# TIDA01398_POWER_PIR.net
KiCad netlist of a schematic drawn in Altium Designer
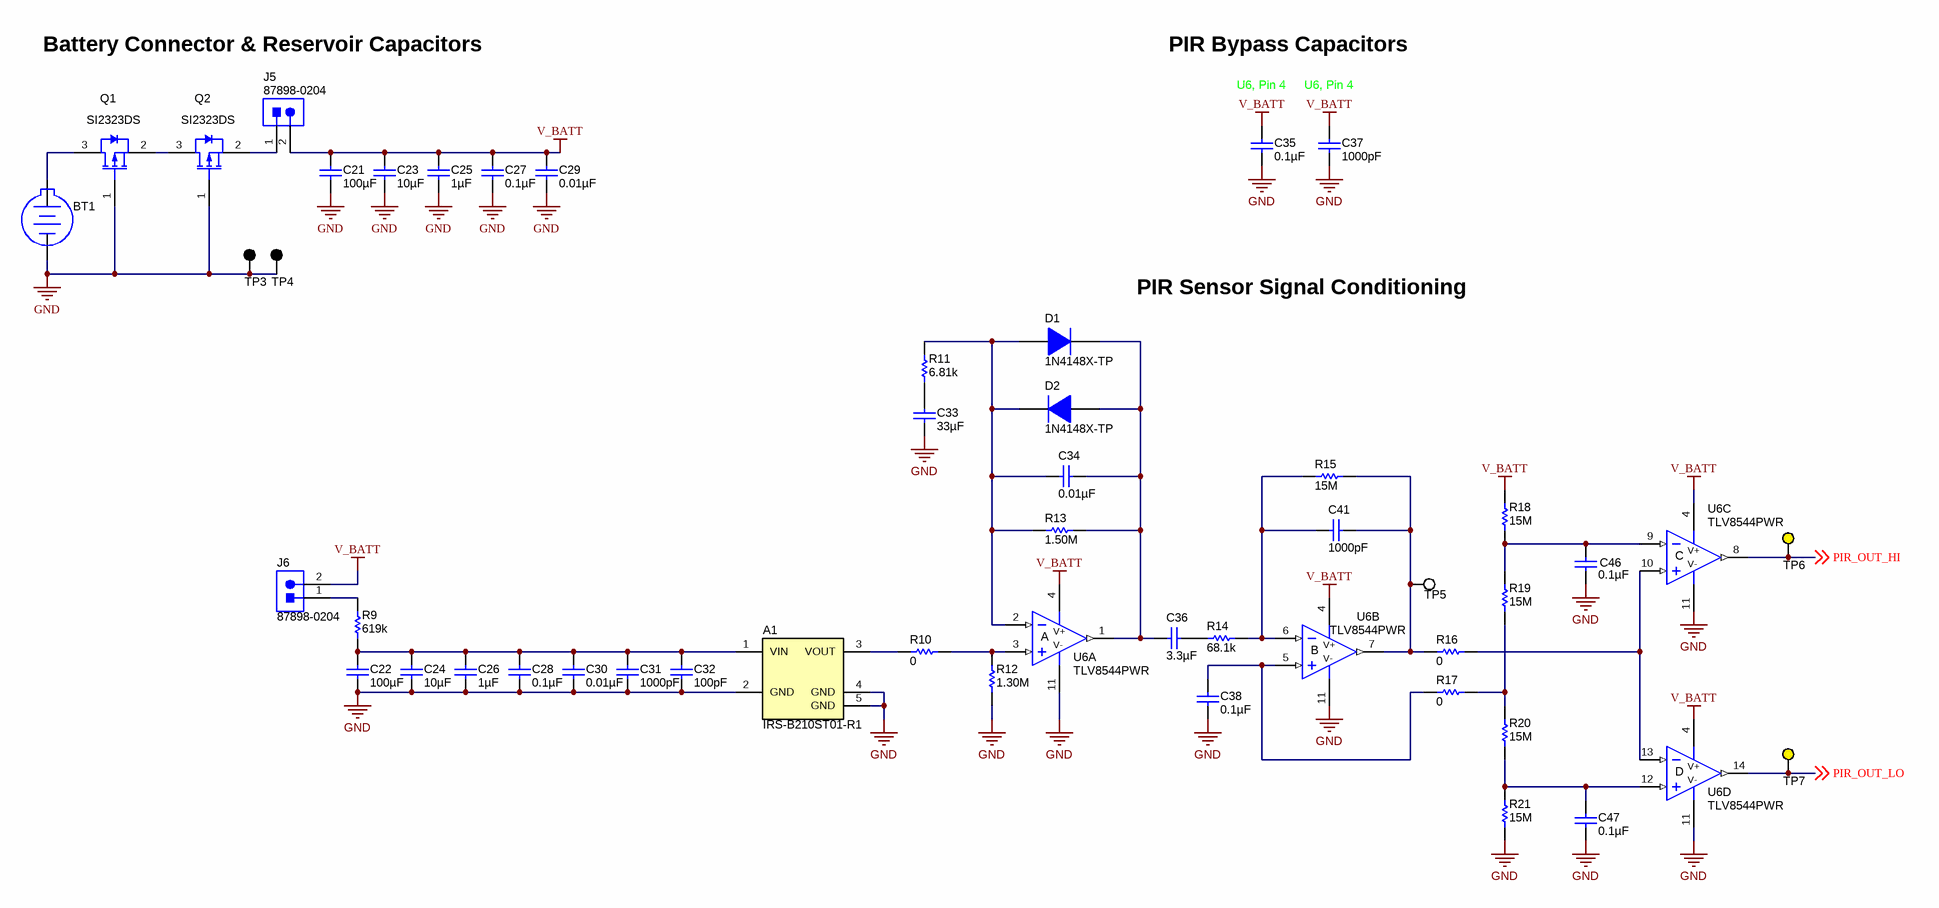
[diagram p0: TIDA01398_POWER_PIR.SchDoc]

(export (version "E")
  (design (tool "Eeschema 10.0.6"))
  (components
    (comp (ref "A1")
      (value "IRS-B210ST01-R1")
      (footprint "Murata_IRS-B210ST01")
      (description "Pyroelectric Infrared Sensors for Reflow Soldering, 3.6mVp-p, SMD")
      (fields
        (field (name "MANUFACTURER") "MuRata")
        (field (name "SYMBOLCREATOR") "Altium")
        (field (name "PUBLISHER") "Texas Instruments")
      )
      (libsource (lib "Other_Passive") (part "IRS-B210ST01-R1"))
    )
    (comp (ref "BT1")
      (value "BS-7")
      (footprint "BAT_BS-7")
      (description "Battery Holder, CR2032, Retainer clip, TH")
      (fields
        (field (name "MANUFACTURER") "Memory Protection Devices")
        (field (name "SYMBOLCREATOR") "a0412235")
        (field (name "PUBLISHER") "Texas Instruments")
      )
      (libsource (lib "Hardware") (part "BS-7"))
    )
    (comp (ref "C21")
      (value "C3216X5R1A107M160AC")
      (footprint "1206_190")
      (description "CAP, CERM, 100 µF, 10 V, +/- 20%, X5R, 1206_190")
      (fields
        (field (name "MANUFACTURER") "TDK")
        (field (name "VALUEDISPLAYED") "100µF")
        (field (name "PUBLISHER") "Texas Instruments")
      )
      (libsource (lib "Capacitor_Ceramic") (part "C3216X5R1A107M160AC"))
    )
    (comp (ref "C22")
      (value "C3216X5R1A107M160AC")
      (footprint "1206_190")
      (description "CAP, CERM, 100 µF, 10 V, +/- 20%, X5R, 1206_190")
      (fields
        (field (name "MANUFACTURER") "TDK")
        (field (name "VALUEDISPLAYED") "100µF")
        (field (name "PUBLISHER") "Texas Instruments")
      )
      (libsource (lib "Capacitor_Ceramic") (part "C3216X5R1A107M160AC"))
    )
    (comp (ref "C23")
      (value "C1608X5R0J106M")
      (footprint "0603")
      (description "CAP, CERM, 10 µF, 6.3 V, +/- 20%, X5R, 0603")
      (fields
        (field (name "VALUEDISPLAYED") "10µF")
        (field (name "MANUFACTURER") "TDK")
        (field (name "PUBLISHER") "Texas Instruments")
      )
      (libsource (lib "Capacitor_Ceramic") (part "C1608X5R0J106M"))
    )
    (comp (ref "C24")
      (value "GRM155R60J106ME44D")
      (footprint "0402")
      (description "CAP, CERM, 10 µF, 6.3 V, +/- 20%, X5R, 0402")
      (fields
        (field (name "VALUEDISPLAYED") "10µF")
        (field (name "MANUFACTURER") "MuRata")
        (field (name "PUBLISHER") "Texas Instruments")
      )
      (libsource (lib "Capacitor_Ceramic") (part "GRM155R60J106ME44D"))
    )
    (comp (ref "C25")
      (value "C1608X7R1C105K")
      (footprint "0603")
      (description "CAP, CERM, 1 µF, 16 V, +/- 10%, X7R, 0603")
      (fields
        (field (name "VALUEDISPLAYED") "1µF")
        (field (name "MANUFACTURER") "TDK")
        (field (name "PUBLISHER") "Texas Instruments")
      )
      (libsource (lib "Capacitor_Ceramic") (part "C1608X7R1C105K"))
    )
    (comp (ref "C26")
      (value "C1005X5R1A105K050BB")
      (footprint "0402")
      (description "CAP, CERM, 1 µF, 10 V, +/- 10%, X5R, 0402")
      (fields
        (field (name "VALUEDISPLAYED") "1µF")
        (field (name "MANUFACTURER") "TDK")
        (field (name "PUBLISHER") "Texas Instruments")
      )
      (libsource (lib "Capacitor_Ceramic") (part "C1005X5R1A105K050BB"))
    )
    (comp (ref "C27")
      (value "C1005X7R1H104K050BB")
      (footprint "0402")
      (description "CAP, CERM, 0.1 µF, 50 V, +/- 10%, X7R, 0402")
      (fields
        (field (name "VALUEDISPLAYED") "0.1µF")
        (field (name "MANUFACTURER") "TDK")
        (field (name "PUBLISHER") "Texas Instruments")
      )
      (libsource (lib "Capacitor_Ceramic") (part "C1005X7R1H104K050BB"))
    )
    (comp (ref "C28")
      (value "C1005X7R1H104K050BB")
      (footprint "0402")
      (description "CAP, CERM, 0.1 µF, 50 V, +/- 10%, X7R, 0402")
      (fields
        (field (name "VALUEDISPLAYED") "0.1µF")
        (field (name "MANUFACTURER") "TDK")
        (field (name "PUBLISHER") "Texas Instruments")
      )
      (libsource (lib "Capacitor_Ceramic") (part "C1005X7R1H104K050BB"))
    )
    (comp (ref "C29")
      (value "C1005X7R1C103K050BA")
      (footprint "0402")
      (description "CAP, CERM, 0.01 µF, 16 V, +/- 10%, X7R, 0402")
      (fields
        (field (name "VALUEDISPLAYED") "0.01µF")
        (field (name "MANUFACTURER") "TDK")
        (field (name "PUBLISHER") "Texas Instruments")
      )
      (libsource (lib "Capacitor_Ceramic") (part "C1005X7R1C103K050BA"))
    )
    (comp (ref "C30")
      (value "C1005X7R1C103K050BA")
      (footprint "0402")
      (description "CAP, CERM, 0.01 µF, 16 V, +/- 10%, X7R, 0402")
      (fields
        (field (name "VALUEDISPLAYED") "0.01µF")
        (field (name "MANUFACTURER") "TDK")
        (field (name "PUBLISHER") "Texas Instruments")
      )
      (libsource (lib "Capacitor_Ceramic") (part "C1005X7R1C103K050BA"))
    )
    (comp (ref "C31")
      (value "C1005X7R1H102K")
      (footprint "0402")
      (description "CAP, CERM, 1000 pF, 50 V, +/- 10%, X7R, 0402")
      (fields
        (field (name "VALUEDISPLAYED") "1000pF")
        (field (name "MANUFACTURER") "TDK")
        (field (name "PUBLISHER") "Texas Instruments")
      )
      (libsource (lib "Capacitor_Ceramic") (part "C1005X7R1H102K"))
    )
    (comp (ref "C32")
      (value "C0402C101J3GACTU")
      (footprint "0402")
      (description "CAP, CERM, 100 pF, 25 V, +/- 5%, C0G/NP0, 0402")
      (fields
        (field (name "VALUEDISPLAYED") "100pF")
        (field (name "MANUFACTURER") "Kemet")
        (field (name "PUBLISHER") "Texas Instruments")
      )
      (libsource (lib "Capacitor_Ceramic") (part "C0402C101J3GACTU"))
    )
    (comp (ref "C33")
      (value "C2012X5R1A336M125AC")
      (footprint "0805_HV")
      (description "CAP, CERM, 33 µF, 10 V, +/- 20%, X5R, 0805")
      (fields
        (field (name "VALUEDISPLAYED") "33µF")
        (field (name "MANUFACTURER") "TDK")
        (field (name "PUBLISHER") "Texas Instruments")
      )
      (libsource (lib "Capacitor_Ceramic") (part "C2012X5R1A336M125AC"))
    )
    (comp (ref "C34")
      (value "C1005X7R1E103K")
      (footprint "0402")
      (description "CAP, CERM, 0.01 µF, 25 V, +/- 10%, X7R, 0402")
      (fields
        (field (name "VALUEDISPLAYED") "0.01µF")
        (field (name "MANUFACTURER") "TDK")
        (field (name "PUBLISHER") "Texas Instruments")
      )
      (libsource (lib "Capacitor_Ceramic") (part "C1005X7R1E103K"))
    )
    (comp (ref "C35")
      (value "C1005X7R1H104K")
      (footprint "0402")
      (description "CAP, CERM, 0.1 µF, 50 V, +/- 10%, X7R, 0402")
      (fields
        (field (name "VALUEDISPLAYED") "0.1µF")
        (field (name "MANUFACTURER") "TDK")
        (field (name "PUBLISHER") "Texas Instruments")
      )
      (libsource (lib "Capacitor_Ceramic") (part "C1005X7R1H104K"))
    )
    (comp (ref "C36")
      (value "C1005X5R1A335K050BC")
      (footprint "0402")
      (description "CAP, CERM, 3.3 µF, 10 V, +/- 10%, X5R, 0402")
      (fields
        (field (name "VALUEDISPLAYED") "3.3µF")
        (field (name "MANUFACTURER") "TDK")
        (field (name "PUBLISHER") "Texas Instruments")
      )
      (libsource (lib "Capacitor_Ceramic") (part "C1005X5R1A335K050BC"))
    )
    (comp (ref "C37")
      (value "C1005X7R1H102K")
      (footprint "0402")
      (description "CAP, CERM, 1000 pF, 50 V, +/- 10%, X7R, 0402")
      (fields
        (field (name "VALUEDISPLAYED") "1000pF")
        (field (name "MANUFACTURER") "TDK")
        (field (name "PUBLISHER") "Texas Instruments")
      )
      (libsource (lib "Capacitor_Ceramic") (part "C1005X7R1H102K"))
    )
    (comp (ref "C38")
      (value "C1005X7R1H104K")
      (footprint "0402")
      (description "CAP, CERM, 0.1 µF, 50 V, +/- 10%, X7R, 0402")
      (fields
        (field (name "VALUEDISPLAYED") "0.1µF")
        (field (name "MANUFACTURER") "TDK")
        (field (name "PUBLISHER") "Texas Instruments")
      )
      (libsource (lib "Capacitor_Ceramic") (part "C1005X7R1H104K"))
    )
    (comp (ref "C41")
      (value "C1005C0G1E102J")
      (footprint "0402")
      (description "CAP, CERM, 1000 pF, 25 V, +/- 5%, C0G/NP0, 0402")
      (fields
        (field (name "VALUEDISPLAYED") "1000pF")
        (field (name "MANUFACTURER") "TDK")
        (field (name "PUBLISHER") "Texas Instruments")
      )
      (libsource (lib "Capacitor_Ceramic") (part "C1005C0G1E102J"))
    )
    (comp (ref "C46")
      (value "C1005X7R1H104K")
      (footprint "0402")
      (description "CAP, CERM, 0.1 µF, 50 V, +/- 10%, X7R, 0402")
      (fields
        (field (name "VALUEDISPLAYED") "0.1µF")
        (field (name "MANUFACTURER") "TDK")
        (field (name "PUBLISHER") "Texas Instruments")
      )
      (libsource (lib "Capacitor_Ceramic") (part "C1005X7R1H104K"))
    )
    (comp (ref "C47")
      (value "C1005X7R1H104K")
      (footprint "0402")
      (description "CAP, CERM, 0.1 µF, 50 V, +/- 10%, X7R, 0402")
      (fields
        (field (name "VALUEDISPLAYED") "0.1µF")
        (field (name "MANUFACTURER") "TDK")
        (field (name "PUBLISHER") "Texas Instruments")
      )
      (libsource (lib "Capacitor_Ceramic") (part "C1005X7R1H104K"))
    )
    (comp (ref "D1")
      (value "1N4148X-TP")
      (footprint "SOD-523")
      (description "Diode, Switching, 75 V, 0.3 A, SOD-523")
      (fields
        (field (name "MANUFACTURER") "Micro Commercial Components")
        (field (name "PUBLISHER") "Texas Instruments")
      )
      (libsource (lib "Diode") (part "1N4148X-TP"))
    )
    (comp (ref "D2")
      (value "1N4148X-TP")
      (footprint "SOD-523")
      (description "Diode, Switching, 75 V, 0.3 A, SOD-523")
      (fields
        (field (name "MANUFACTURER") "Micro Commercial Components")
        (field (name "PUBLISHER") "Texas Instruments")
      )
      (libsource (lib "Diode") (part "1N4148X-TP"))
    )
    (comp (ref "J5")
      (value "87898-0204")
      (footprint "Molex_87898-0204")
      (description "Header, 2.54 mm, 2x1, Gold, R/A, SMT")
      (fields
        (field (name "MANUFACTURER") "Molex")
        (field (name "SYMBOLCREATOR") "a0412235")
        (field (name "PUBLISHER") "Texas Instruments")
      )
      (libsource (lib "") (part "87898-0204_1"))
    )
    (comp (ref "J6")
      (value "87898-0204")
      (footprint "Molex_87898-0204")
      (description "Header, 2.54 mm, 2x1, Gold, R/A, SMT")
      (fields
        (field (name "MANUFACTURER") "Molex")
        (field (name "SYMBOLCREATOR") "a0412235")
        (field (name "PUBLISHER") "Texas Instruments")
      )
      (libsource (lib "Connectors_Molex") (part "87898-0204"))
    )
    (comp (ref "Q1")
      (value "SI2323DS")
      (footprint "SOT-23")
      (description "MOSFET, P-CH, -20 V, -3.7 A, SOT-23")
      (fields (field (name "MANUFACTURER") "Vishay-Siliconix") (field (name "PUBLISHER") "Texas Instruments"))
      (libsource (lib "FETs") (part "SI2323DS"))
    )
    (comp (ref "Q2")
      (value "SI2323DS")
      (footprint "SOT-23")
      (description "MOSFET, P-CH, -20 V, -3.7 A, SOT-23")
      (fields (field (name "MANUFACTURER") "Vishay-Siliconix") (field (name "PUBLISHER") "Texas Instruments"))
      (libsource (lib "FETs") (part "SI2323DS"))
    )
    (comp (ref "R9")
      (value "CRCW0402619KFKED")
      (footprint "0402")
      (description "RES, 619 k, 1%, 0.063 W, 0402")
      (fields
        (field (name "VALUEDISPLAYED") "619k")
        (field (name "MANUFACTURER") "Vishay-Dale")
        (field (name "PUBLISHER") "Texas Instruments")
      )
      (libsource (lib "Resistor_0402") (part "CRCW0402619KFKED"))
    )
    (comp (ref "R10")
      (value "CRCW04020000Z0ED")
      (footprint "0402")
      (description "RES, 0, 5%, 0.063 W, 0402")
      (fields
        (field (name "VALUEDISPLAYED") "0")
        (field (name "MANUFACTURER") "Vishay-Dale")
        (field (name "PUBLISHER") "Texas Instruments")
      )
      (libsource (lib "Resistor_0402") (part "CRCW04020000Z0ED"))
    )
    (comp (ref "R11")
      (value "CRCW04026K81FKED")
      (footprint "0402")
      (description "RES, 6.81 k, 1%, 0.063 W, 0402")
      (fields
        (field (name "VALUEDISPLAYED") "6.81k")
        (field (name "MANUFACTURER") "Vishay-Dale")
        (field (name "PUBLISHER") "Texas Instruments")
      )
      (libsource (lib "Resistor_0402") (part "CRCW04026K81FKED"))
    )
    (comp (ref "R12")
      (value "CRCW04021M30FKED")
      (footprint "0402")
      (description "RES, 1.30 M, 1%, 0.063 W, 0402")
      (fields
        (field (name "VALUEDISPLAYED") "1.30M")
        (field (name "MANUFACTURER") "Vishay-Dale")
        (field (name "PUBLISHER") "Texas Instruments")
      )
      (libsource (lib "Resistor_0402") (part "CRCW04021M30FKED"))
    )
    (comp (ref "R13")
      (value "CRCW04021M50FKED")
      (footprint "0402")
      (description "RES, 1.50 M, 1%, 0.063 W, 0402")
      (fields
        (field (name "VALUEDISPLAYED") "1.50M")
        (field (name "MANUFACTURER") "Vishay-Dale")
        (field (name "PUBLISHER") "Texas Instruments")
      )
      (libsource (lib "Resistor_0402") (part "CRCW04021M50FKED"))
    )
    (comp (ref "R14")
      (value "CRCW040268K1FKED")
      (footprint "0402")
      (description "RES, 68.1 k, 1%, 0.063 W, 0402")
      (fields
        (field (name "VALUEDISPLAYED") "68.1k")
        (field (name "MANUFACTURER") "Vishay-Dale")
        (field (name "PUBLISHER") "Texas Instruments")
      )
      (libsource (lib "Resistor_0402") (part "CRCW040268K1FKED"))
    )
    (comp (ref "R15")
      (value "RMCF0805JT15M0")
      (footprint "0805_HV")
      (description "RES, 15 M, 5%, 0.125 W, AEC-Q200 Grade 0, 0805")
      (fields
        (field (name "VALUEDISPLAYED") "15M")
        (field (name "MANUFACTURER") "Stackpole Electronics Inc")
        (field (name "PUBLISHER") "Texas Instruments")
      )
      (libsource (lib "Resistor_0805") (part "RMCF0805JT15M0"))
    )
    (comp (ref "R16")
      (value "CRCW04020000Z0ED")
      (footprint "0402")
      (description "RES, 0, 5%, 0.063 W, 0402")
      (fields
        (field (name "VALUEDISPLAYED") "0")
        (field (name "MANUFACTURER") "Vishay-Dale")
        (field (name "PUBLISHER") "Texas Instruments")
      )
      (libsource (lib "Resistor_0402") (part "CRCW04020000Z0ED"))
    )
    (comp (ref "R17")
      (value "CRCW04020000Z0ED")
      (footprint "0402")
      (description "RES, 0, 5%, 0.063 W, 0402")
      (fields
        (field (name "VALUEDISPLAYED") "0")
        (field (name "MANUFACTURER") "Vishay-Dale")
        (field (name "PUBLISHER") "Texas Instruments")
      )
      (libsource (lib "Resistor_0402") (part "CRCW04020000Z0ED"))
    )
    (comp (ref "R18")
      (value "RMCF0805JT15M0")
      (footprint "0805_HV")
      (description "RES, 15 M, 5%, 0.125 W, AEC-Q200 Grade 0, 0805")
      (fields
        (field (name "VALUEDISPLAYED") "15M")
        (field (name "MANUFACTURER") "Stackpole Electronics Inc")
        (field (name "PUBLISHER") "Texas Instruments")
      )
      (libsource (lib "Resistor_0805") (part "RMCF0805JT15M0"))
    )
    (comp (ref "R19")
      (value "RMCF0805JT15M0")
      (footprint "0805_HV")
      (description "RES, 15 M, 5%, 0.125 W, AEC-Q200 Grade 0, 0805")
      (fields
        (field (name "VALUEDISPLAYED") "15M")
        (field (name "MANUFACTURER") "Stackpole Electronics Inc")
        (field (name "PUBLISHER") "Texas Instruments")
      )
      (libsource (lib "Resistor_0805") (part "RMCF0805JT15M0"))
    )
    (comp (ref "R20")
      (value "RMCF0805JT15M0")
      (footprint "0805_HV")
      (description "RES, 15 M, 5%, 0.125 W, AEC-Q200 Grade 0, 0805")
      (fields
        (field (name "VALUEDISPLAYED") "15M")
        (field (name "MANUFACTURER") "Stackpole Electronics Inc")
        (field (name "PUBLISHER") "Texas Instruments")
      )
      (libsource (lib "Resistor_0805") (part "RMCF0805JT15M0"))
    )
    (comp (ref "R21")
      (value "RMCF0805JT15M0")
      (footprint "0805_HV")
      (description "RES, 15 M, 5%, 0.125 W, AEC-Q200 Grade 0, 0805")
      (fields
        (field (name "VALUEDISPLAYED") "15M")
        (field (name "MANUFACTURER") "Stackpole Electronics Inc")
        (field (name "PUBLISHER") "Texas Instruments")
      )
      (libsource (lib "Resistor_0805") (part "RMCF0805JT15M0"))
    )
    (comp (ref "TP3")
      (value "5001")
      (footprint "Keystone5001")
      (description "Test Point, Miniature, Black, TH")
      (fields (field (name "MANUFACTURER") "Keystone") (field (name "PUBLISHER") "Texas Instruments"))
      (libsource (lib "Connectors_Keystone") (part "5001"))
    )
    (comp (ref "TP4")
      (value "5001")
      (footprint "Keystone5001")
      (description "Test Point, Miniature, Black, TH")
      (fields (field (name "MANUFACTURER") "Keystone") (field (name "PUBLISHER") "Texas Instruments"))
      (libsource (lib "Connectors_Keystone") (part "5001"))
    )
    (comp (ref "TP5")
      (value "5015")
      (footprint "Testpoint_Keystone_Miniature")
      (description "Test Point, Miniature, SMT")
      (fields (field (name "MANUFACTURER") "Keystone") (field (name "PUBLISHER") "Texas Instruments"))
      (libsource (lib "Connectors_Keystone") (part "5015"))
    )
    (comp (ref "TP6")
      (value "5004")
      (footprint "Keystone5004")
      (description "Test Point, Miniature, Yellow, TH")
      (fields (field (name "MANUFACTURER") "Keystone") (field (name "PUBLISHER") "Texas Instruments"))
      (libsource (lib "Connectors_Keystone") (part "5004"))
    )
    (comp (ref "TP7")
      (value "5004")
      (footprint "Keystone5004")
      (description "Test Point, Miniature, Yellow, TH")
      (fields (field (name "MANUFACTURER") "Keystone") (field (name "PUBLISHER") "Texas Instruments"))
      (libsource (lib "Connectors_Keystone") (part "5004"))
    )
    (comp (ref "U6")
      (value "TLV8544PWR")
      (footprint "PW0014A_N")
      (description "500 nA RRIO Nanopower Operational Amplifier, PW0014A (TSSOP-14)")
      (fields
        (field (name "ALTERNATE PARTNUMBER") "TLV8544PWT")
        (field (name "MANUFACTURER") "Texas Instruments")
        (field (name "SYMBOLCREATOR") "a0412235")
        (field (name "PUBLISHER") "Texas Instruments")
      )
      (libsource (lib "TI_Pre_RTM") (part "TLV8544PWR"))
    )
  )
  (nets
    (net (code "1") (name "GND") (class "Default")
      (node (ref "A1") (pin "2") (pinfunction "GND_2") (pintype "power_in"))
      (node (ref "A1") (pin "4") (pinfunction "GND_4") (pintype "power_in"))
      (node (ref "A1") (pin "5") (pinfunction "GND_5") (pintype "power_in"))
      (node (ref "BT1") (pin "2") (pinfunction "-_2") (pintype "passive"))
      (node (ref "C21") (pin "2") (pinfunction "2_2") (pintype "passive"))
      (node (ref "C22") (pin "2") (pinfunction "2_2") (pintype "passive"))
      (node (ref "C23") (pin "2") (pinfunction "2_2") (pintype "passive"))
      (node (ref "C24") (pin "2") (pinfunction "2_2") (pintype "passive"))
      (node (ref "C25") (pin "2") (pinfunction "2_2") (pintype "passive"))
      (node (ref "C26") (pin "2") (pinfunction "2_2") (pintype "passive"))
      (node (ref "C27") (pin "2") (pinfunction "2_2") (pintype "passive"))
      (node (ref "C28") (pin "2") (pinfunction "2_2") (pintype "passive"))
      (node (ref "C29") (pin "2") (pinfunction "2_2") (pintype "passive"))
      (node (ref "C30") (pin "2") (pinfunction "2_2") (pintype "passive"))
      (node (ref "C31") (pin "2") (pinfunction "2_2") (pintype "passive"))
      (node (ref "C32") (pin "2") (pinfunction "2_2") (pintype "passive"))
      (node (ref "C33") (pin "2") (pinfunction "2_2") (pintype "passive"))
      (node (ref "C35") (pin "1") (pinfunction "1_1") (pintype "passive"))
      (node (ref "C37") (pin "2") (pinfunction "2_2") (pintype "passive"))
      (node (ref "C38") (pin "2") (pinfunction "2_2") (pintype "passive"))
      (node (ref "C46") (pin "2") (pinfunction "2_2") (pintype "passive"))
      (node (ref "C47") (pin "2") (pinfunction "2_2") (pintype "passive"))
      (node (ref "Q1") (pin "1") (pinfunction "G_1") (pintype "passive"))
      (node (ref "Q2") (pin "1") (pinfunction "G_1") (pintype "passive"))
      (node (ref "R12") (pin "1") (pinfunction "1_1") (pintype "passive"))
      (node (ref "R21") (pin "1") (pinfunction "1_1") (pintype "passive"))
      (node (ref "TP3") (pin "1") (pintype "passive"))
      (node (ref "TP4") (pin "1") (pintype "passive"))
      (node (ref "U6") (pin "11") (pinfunction "V-_11") (pintype "power_in"))
    )
    (net (code "2") (name "Net-(A1-VIN)") (class "Default")
      (node (ref "A1") (pin "1") (pinfunction "VIN_1") (pintype "power_in"))
      (node (ref "C22") (pin "1") (pinfunction "1_1") (pintype "passive"))
      (node (ref "C24") (pin "1") (pinfunction "1_1") (pintype "passive"))
      (node (ref "C26") (pin "1") (pinfunction "1_1") (pintype "passive"))
      (node (ref "C28") (pin "1") (pinfunction "1_1") (pintype "passive"))
      (node (ref "C30") (pin "1") (pinfunction "1_1") (pintype "passive"))
      (node (ref "C31") (pin "1") (pinfunction "1_1") (pintype "passive"))
      (node (ref "C32") (pin "1") (pinfunction "1_1") (pintype "passive"))
      (node (ref "R9") (pin "1") (pinfunction "1_1") (pintype "passive"))
    )
    (net (code "3") (name "Net-(A1-VOUT)") (class "Default")
      (node (ref "A1") (pin "3") (pinfunction "VOUT_3") (pintype "power_in"))
      (node (ref "R10") (pin "1") (pinfunction "1_1") (pintype "passive"))
    )
    (net (code "4") (name "Net-(BT1-+)") (class "Default")
      (node (ref "BT1") (pin "1") (pinfunction "+_1") (pintype "passive"))
      (node (ref "Q1") (pin "3") (pinfunction "D_3") (pintype "passive"))
    )
    (net (code "5") (name "Net-(C33-Pad1)") (class "Default")
      (node (ref "C33") (pin "1") (pinfunction "1_1") (pintype "passive"))
      (node (ref "R11") (pin "1") (pinfunction "1_1") (pintype "passive"))
    )
    (net (code "6") (name "Net-(C36-Pad1)") (class "Default")
      (node (ref "C36") (pin "1") (pinfunction "1_1") (pintype "passive"))
      (node (ref "R14") (pin "1") (pinfunction "1_1") (pintype "passive"))
    )
    (net (code "7") (name "Net-(D1-A)") (class "Default")
      (node (ref "C34") (pin "2") (pinfunction "2_2") (pintype "passive"))
      (node (ref "D1") (pin "2") (pinfunction "A_2") (pintype "passive"))
      (node (ref "D2") (pin "1") (pinfunction "K_1") (pintype "passive"))
      (node (ref "R11") (pin "2") (pinfunction "2_2") (pintype "passive"))
      (node (ref "R13") (pin "1") (pinfunction "1_1") (pintype "passive"))
      (node (ref "U6") (pin "2") (pinfunction "IN-_2") (pintype "input"))
    )
    (net (code "8") (name "Net-(D1-K)") (class "Default")
      (node (ref "C34") (pin "1") (pinfunction "1_1") (pintype "passive"))
      (node (ref "C36") (pin "2") (pinfunction "2_2") (pintype "passive"))
      (node (ref "D1") (pin "1") (pinfunction "K_1") (pintype "passive"))
      (node (ref "D2") (pin "2") (pinfunction "A_2") (pintype "passive"))
      (node (ref "R13") (pin "2") (pinfunction "2_2") (pintype "passive"))
      (node (ref "U6") (pin "1") (pinfunction "OUT_1") (pintype "output"))
    )
    (net (code "9") (name "Net-(J6-Pad1)") (class "Default")
      (node (ref "J6") (pin "1") (pinfunction "1_1") (pintype "passive"))
      (node (ref "R9") (pin "2") (pinfunction "2_2") (pintype "passive"))
    )
    (net (code "10") (name "Net-(Q1-S)") (class "Default")
      (node (ref "Q1") (pin "2") (pinfunction "S_2") (pintype "passive"))
      (node (ref "Q2") (pin "3") (pinfunction "D_3") (pintype "passive"))
    )
    (net (code "11") (name "Net-(Q2-S)") (class "Default")
      (node (ref "J5") (pin "1") (pinfunction "1_1") (pintype "passive"))
      (node (ref "Q2") (pin "2") (pinfunction "S_2") (pintype "passive"))
    )
    (net (code "12") (name "Net-(R17-Pad2)") (class "Default")
      (node (ref "R17") (pin "2") (pinfunction "2_2") (pintype "passive"))
      (node (ref "R19") (pin "1") (pinfunction "1_1") (pintype "passive"))
      (node (ref "R20") (pin "2") (pinfunction "2_2") (pintype "passive"))
    )
    (net (code "13") (name "Net-(U6A-IN+)") (class "Default")
      (node (ref "R10") (pin "2") (pinfunction "2_2") (pintype "passive"))
      (node (ref "R12") (pin "2") (pinfunction "2_2") (pintype "passive"))
      (node (ref "U6") (pin "3") (pinfunction "IN+_3") (pintype "input"))
    )
    (net (code "14") (name "Net-(U6B-IN+)") (class "Default")
      (node (ref "C38") (pin "1") (pinfunction "1_1") (pintype "passive"))
      (node (ref "R17") (pin "1") (pinfunction "1_1") (pintype "passive"))
      (node (ref "U6") (pin "5") (pinfunction "IN+_5") (pintype "input"))
    )
    (net (code "15") (name "Net-(U6B-IN-)") (class "Default")
      (node (ref "C41") (pin "2") (pinfunction "2_2") (pintype "passive"))
      (node (ref "R14") (pin "2") (pinfunction "2_2") (pintype "passive"))
      (node (ref "R15") (pin "1") (pinfunction "1_1") (pintype "passive"))
      (node (ref "U6") (pin "6") (pinfunction "IN-_6") (pintype "input"))
    )
    (net (code "16") (name "Net-(U6B-OUT)") (class "Default")
      (node (ref "C41") (pin "1") (pinfunction "1_1") (pintype "passive"))
      (node (ref "R15") (pin "2") (pinfunction "2_2") (pintype "passive"))
      (node (ref "R16") (pin "1") (pinfunction "1_1") (pintype "passive"))
      (node (ref "TP5") (pin "1") (pintype "passive"))
      (node (ref "U6") (pin "7") (pinfunction "OUT_7") (pintype "output"))
    )
    (net (code "17") (name "Net-(U6C-IN+)") (class "Default")
      (node (ref "R16") (pin "2") (pinfunction "2_2") (pintype "passive"))
      (node (ref "U6") (pin "10") (pinfunction "IN+_10") (pintype "input"))
      (node (ref "U6") (pin "13") (pinfunction "IN-_13") (pintype "input"))
    )
    (net (code "18") (name "Net-(U6C-IN-)") (class "Default")
      (node (ref "C46") (pin "1") (pinfunction "1_1") (pintype "passive"))
      (node (ref "R18") (pin "1") (pinfunction "1_1") (pintype "passive"))
      (node (ref "R19") (pin "2") (pinfunction "2_2") (pintype "passive"))
      (node (ref "U6") (pin "9") (pinfunction "IN-_9") (pintype "input"))
    )
    (net (code "19") (name "Net-(U6D-IN+)") (class "Default")
      (node (ref "C47") (pin "1") (pinfunction "1_1") (pintype "passive"))
      (node (ref "R20") (pin "1") (pinfunction "1_1") (pintype "passive"))
      (node (ref "R21") (pin "2") (pinfunction "2_2") (pintype "passive"))
      (node (ref "U6") (pin "12") (pinfunction "IN+_12") (pintype "input"))
    )
    (net (code "20") (name "PIR_OUT_HI") (class "Default")
      (node (ref "TP6") (pin "1") (pintype "passive"))
      (node (ref "U6") (pin "8") (pinfunction "OUT_8") (pintype "output"))
    )
    (net (code "21") (name "PIR_OUT_LO") (class "Default")
      (node (ref "TP7") (pin "1") (pintype "passive"))
      (node (ref "U6") (pin "14") (pinfunction "OUT_14") (pintype "output"))
    )
    (net (code "22") (name "V_BATT") (class "Default")
      (node (ref "C21") (pin "1") (pinfunction "1_1") (pintype "passive"))
      (node (ref "C23") (pin "1") (pinfunction "1_1") (pintype "passive"))
      (node (ref "C25") (pin "1") (pinfunction "1_1") (pintype "passive"))
      (node (ref "C27") (pin "1") (pinfunction "1_1") (pintype "passive"))
      (node (ref "C29") (pin "1") (pinfunction "1_1") (pintype "passive"))
      (node (ref "C35") (pin "2") (pinfunction "2_2") (pintype "passive"))
      (node (ref "C37") (pin "1") (pinfunction "1_1") (pintype "passive"))
      (node (ref "J5") (pin "2") (pinfunction "2_2") (pintype "passive"))
      (node (ref "J6") (pin "2") (pinfunction "2_2") (pintype "passive"))
      (node (ref "R18") (pin "2") (pinfunction "2_2") (pintype "passive"))
      (node (ref "U6") (pin "4") (pinfunction "V+_4") (pintype "power_in"))
    )
  )
)
